# debounce_v0_1.net
KiCad netlist of a schematic drawn in EAGLE
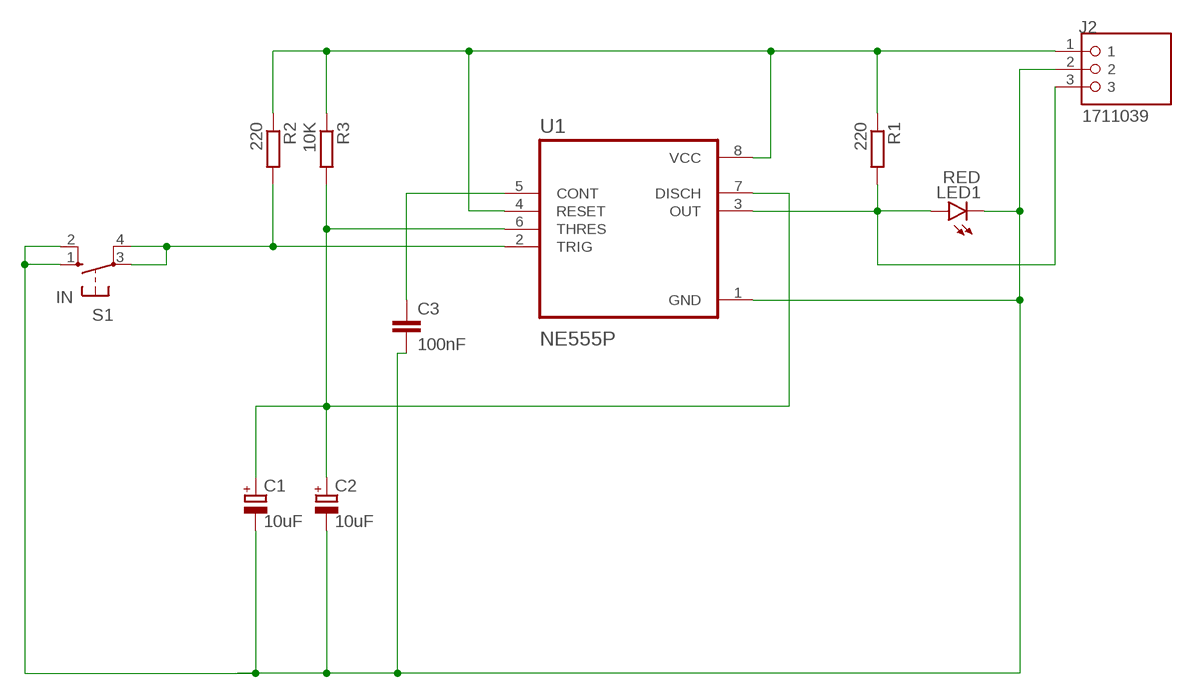
[diagram p0: schematic, sheet 1]

(export (version "E")
  (design (tool "Eeschema 10.0.6"))
  (components
    (comp (ref "C1")
      (value "10uF")
      (footprint "eagle-import:E2,5-6")
      (libsource (lib "eagle-import") (part "CPOL-EUE2.5-6"))
    )
    (comp (ref "C2")
      (value "10uF")
      (footprint "eagle-import:E2,5-6")
      (libsource (lib "eagle-import") (part "CPOL-EUE2.5-6"))
    )
    (comp (ref "C3")
      (value "100nF")
      (footprint "eagle-import:RCL_C025-025X050")
      (libsource (lib "eagle-import") (part "RCL_C-EU025-025X050"))
    )
    (comp (ref "J2")
      (value "1711039")
      (footprint "eagle-import:PHOENIX_1711039")
      (fields (field (name "MF") "Phoenix Contact"))
      (libsource (lib "eagle-import") (part "1711039"))
    )
    (comp (ref "LED1")
      (value "RED")
      (footprint "eagle-import:LED3MM")
      (libsource (lib "eagle-import") (part "LED3MM"))
    )
    (comp (ref "R1")
      (value "220")
      (footprint "eagle-import:RCL_0207_7")
      (libsource (lib "eagle-import") (part "RCL_R-EU_0207/7"))
    )
    (comp (ref "R2")
      (value "220")
      (footprint "eagle-import:RCL_0207_7")
      (libsource (lib "eagle-import") (part "RCL_R-EU_0207/7"))
    )
    (comp (ref "R3")
      (value "10K")
      (footprint "eagle-import:RCL_0207_7")
      (libsource (lib "eagle-import") (part "RCL_R-EU_0207/7"))
    )
    (comp (ref "S1")
      (value "IN")
      (footprint "eagle-import:B3F-10XX")
      (fields (field (name "MPN") "B3F-1000"))
      (libsource (lib "eagle-import") (part "10-XX"))
    )
    (comp (ref "U1")
      (value "NE555P")
      (footprint "eagle-import:DIP794W45P254L959H508Q8")
      (fields (field (name "MF") "Texas Instruments"))
      (libsource (lib "eagle-import") (part "NE555P"))
    )
  )
  (nets
    (net (code "1") (name "Net-(LED1-C)") (class "Default")
      (node (ref "C1") (pin "-") (pinfunction "-_-") (pintype "passive"))
      (node (ref "C2") (pin "-") (pinfunction "-_-") (pintype "passive"))
      (node (ref "C3") (pin "2") (pinfunction "2_2") (pintype "passive"))
      (node (ref "J2") (pin "2") (pinfunction "2_2") (pintype "passive"))
      (node (ref "LED1") (pin "K") (pinfunction "C_K") (pintype "passive"))
      (node (ref "S1") (pin "1") (pinfunction "S_1") (pintype "passive"))
      (node (ref "S1") (pin "2") (pinfunction "S1_2") (pintype "passive"))
      (node (ref "U1") (pin "1") (pinfunction "GND_1") (pintype "power_in"))
    )
    (net (code "2") (name "Net-(S1-P)") (class "Default")
      (node (ref "R2") (pin "2") (pinfunction "2_2") (pintype "passive"))
      (node (ref "S1") (pin "3") (pinfunction "P_3") (pintype "passive"))
      (node (ref "S1") (pin "4") (pinfunction "P1_4") (pintype "passive"))
      (node (ref "U1") (pin "2") (pinfunction "TRIG_2") (pintype "input"))
    )
    (net (code "3") (name "Net-(U1-CONT)") (class "Default")
      (node (ref "C3") (pin "1") (pinfunction "1_1") (pintype "passive"))
      (node (ref "U1") (pin "5") (pinfunction "CONT_5") (pintype "input"))
    )
    (net (code "4") (name "Net-(U1-DISCH)") (class "Default")
      (node (ref "C1") (pin "+") (pinfunction "+_+") (pintype "passive"))
      (node (ref "C2") (pin "+") (pinfunction "+_+") (pintype "passive"))
      (node (ref "R3") (pin "2") (pinfunction "2_2") (pintype "passive"))
      (node (ref "U1") (pin "6") (pinfunction "THRES_6") (pintype "input"))
      (node (ref "U1") (pin "7") (pinfunction "DISCH_7") (pintype "output"))
    )
    (net (code "5") (name "Net-(U1-OUT)") (class "Default")
      (node (ref "J2") (pin "3") (pinfunction "3_3") (pintype "passive"))
      (node (ref "LED1") (pin "A") (pinfunction "A_A") (pintype "passive"))
      (node (ref "R1") (pin "2") (pinfunction "2_2") (pintype "passive"))
      (node (ref "U1") (pin "3") (pinfunction "OUT_3") (pintype "output"))
    )
    (net (code "6") (name "Net-(U1-RESET)") (class "Default")
      (node (ref "J2") (pin "1") (pinfunction "1_1") (pintype "passive"))
      (node (ref "R1") (pin "1") (pinfunction "1_1") (pintype "passive"))
      (node (ref "R2") (pin "1") (pinfunction "1_1") (pintype "passive"))
      (node (ref "R3") (pin "1") (pinfunction "1_1") (pintype "passive"))
      (node (ref "U1") (pin "4") (pinfunction "RESET_4") (pintype "input"))
      (node (ref "U1") (pin "8") (pinfunction "VCC_8") (pintype "power_in"))
    )
  )
)
